# 20250814.net
KiCad netlist of a schematic drawn in EasyEDA Pro
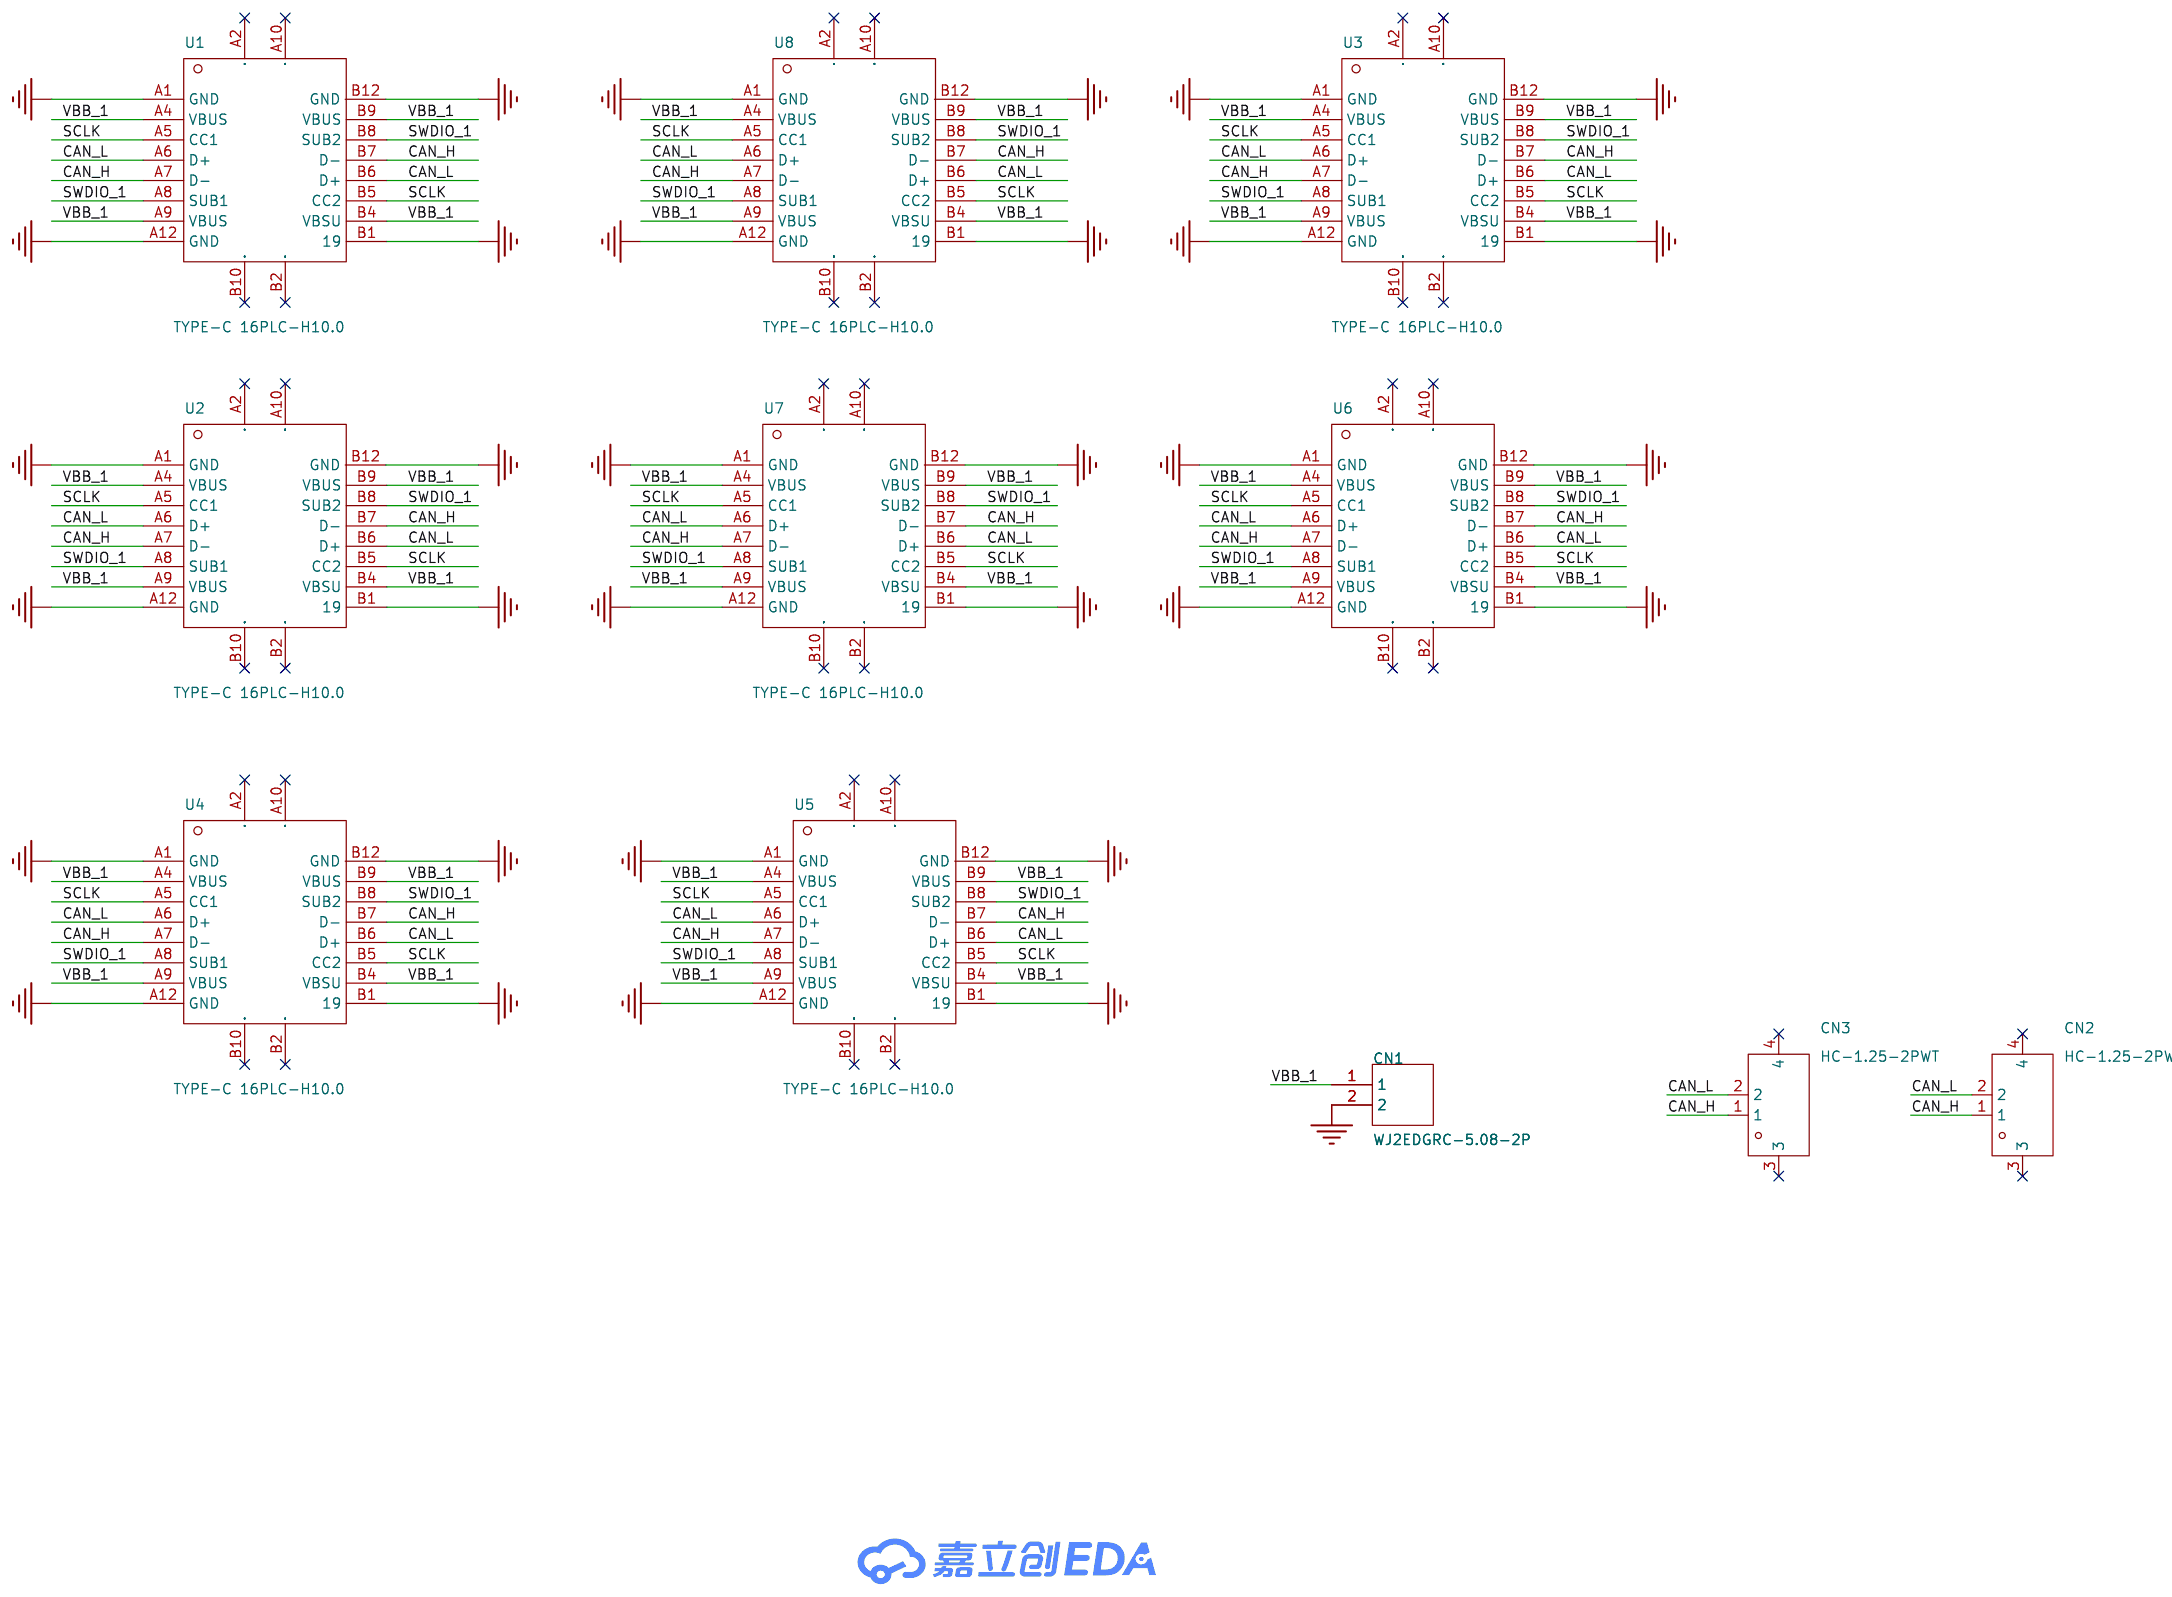
[diagram p0: schematic sheet]

(export (version "E")
  (design (tool "Eeschema 10.0.6"))
  (components
    (comp (ref "CN1")
      (value "WJ2EDGRC-5.08-2P")
      (footprint "easyedapro:CONN-TH_2P-P5.08_WJ2EDGRC-5.08-2P")
      (fields (field (name "Manufacturer") "KANGNEX(康奈克斯电气)"))
      (libsource (lib "easyedapro") (part "WJ2EDGRC-5.08-2P"))
    )
    (comp (ref "CN2")
      (value "HC-1.25-2PWT")
      (footprint "easyedapro:CONN-SMD_2P-P1.25-HC-1.25-2PWT")
      (fields (field (name "Manufacturer") "HCTL(华灿天禄)"))
      (libsource (lib "easyedapro") (part "HC-1.25-2PWT"))
    )
    (comp (ref "CN3")
      (value "HC-1.25-2PWT")
      (footprint "easyedapro:CONN-SMD_2P-P1.25-HC-1.25-2PWT")
      (fields (field (name "Manufacturer") "HCTL(华灿天禄)"))
      (libsource (lib "easyedapro") (part "HC-1.25-2PWT"))
    )
    (comp (ref "U1")
      (value "TYPE-C 16PLC-H10.0")
      (footprint "easyedapro:TYPE-C-TH_16PLC-H10.0")
      (fields (field (name "Manufacturer") "SHOU HAN(首韩)"))
      (libsource (lib "easyedapro") (part "TYPE-C 16PLC-H10.0"))
    )
    (comp (ref "U2")
      (value "TYPE-C 16PLC-H10.0")
      (footprint "easyedapro:TYPE-C-TH_16PLC-H10.0")
      (fields (field (name "Manufacturer") "SHOU HAN(首韩)"))
      (libsource (lib "easyedapro") (part "TYPE-C 16PLC-H10.0"))
    )
    (comp (ref "U3")
      (value "TYPE-C 16PLC-H10.0")
      (footprint "easyedapro:TYPE-C-TH_16PLC-H10.0")
      (fields (field (name "Manufacturer") "SHOU HAN(首韩)"))
      (libsource (lib "easyedapro") (part "TYPE-C 16PLC-H10.0"))
    )
    (comp (ref "U4")
      (value "TYPE-C 16PLC-H10.0")
      (footprint "easyedapro:TYPE-C-TH_16PLC-H10.0")
      (fields (field (name "Manufacturer") "SHOU HAN(首韩)"))
      (libsource (lib "easyedapro") (part "TYPE-C 16PLC-H10.0"))
    )
    (comp (ref "U5")
      (value "TYPE-C 16PLC-H10.0")
      (footprint "easyedapro:TYPE-C-TH_16PLC-H10.0")
      (fields (field (name "Manufacturer") "SHOU HAN(首韩)"))
      (libsource (lib "easyedapro") (part "TYPE-C 16PLC-H10.0"))
    )
    (comp (ref "U6")
      (value "TYPE-C 16PLC-H10.0")
      (footprint "easyedapro:TYPE-C-TH_16PLC-H10.0")
      (fields (field (name "Manufacturer") "SHOU HAN(首韩)"))
      (libsource (lib "easyedapro") (part "TYPE-C 16PLC-H10.0"))
    )
    (comp (ref "U7")
      (value "TYPE-C 16PLC-H10.0")
      (footprint "easyedapro:TYPE-C-TH_16PLC-H10.0")
      (fields (field (name "Manufacturer") "SHOU HAN(首韩)"))
      (libsource (lib "easyedapro") (part "TYPE-C 16PLC-H10.0"))
    )
    (comp (ref "U8")
      (value "TYPE-C 16PLC-H10.0")
      (footprint "easyedapro:TYPE-C-TH_16PLC-H10.0")
      (fields (field (name "Manufacturer") "SHOU HAN(首韩)"))
      (libsource (lib "easyedapro") (part "TYPE-C 16PLC-H10.0"))
    )
  )
  (nets
    (net (code "1") (name "/CAN_H") (class "Default")
      (node (ref "CN2") (pin "1") (pinfunction "1_1") (pintype "unspecified"))
      (node (ref "CN3") (pin "1") (pinfunction "1_1") (pintype "unspecified"))
      (node (ref "U1") (pin "A7") (pinfunction "D-_A7") (pintype "input"))
      (node (ref "U1") (pin "B7") (pinfunction "D-_B7") (pintype "input"))
      (node (ref "U2") (pin "A7") (pinfunction "D-_A7") (pintype "input"))
      (node (ref "U2") (pin "B7") (pinfunction "D-_B7") (pintype "input"))
      (node (ref "U3") (pin "A7") (pinfunction "D-_A7") (pintype "input"))
      (node (ref "U3") (pin "B7") (pinfunction "D-_B7") (pintype "input"))
      (node (ref "U4") (pin "A7") (pinfunction "D-_A7") (pintype "input"))
      (node (ref "U4") (pin "B7") (pinfunction "D-_B7") (pintype "input"))
      (node (ref "U5") (pin "A7") (pinfunction "D-_A7") (pintype "input"))
      (node (ref "U5") (pin "B7") (pinfunction "D-_B7") (pintype "input"))
      (node (ref "U6") (pin "A7") (pinfunction "D-_A7") (pintype "input"))
      (node (ref "U6") (pin "B7") (pinfunction "D-_B7") (pintype "input"))
      (node (ref "U7") (pin "A7") (pinfunction "D-_A7") (pintype "input"))
      (node (ref "U7") (pin "B7") (pinfunction "D-_B7") (pintype "input"))
      (node (ref "U8") (pin "A7") (pinfunction "D-_A7") (pintype "input"))
      (node (ref "U8") (pin "B7") (pinfunction "D-_B7") (pintype "input"))
    )
    (net (code "2") (name "/CAN_L") (class "Default")
      (node (ref "CN2") (pin "2") (pinfunction "2_2") (pintype "unspecified"))
      (node (ref "CN3") (pin "2") (pinfunction "2_2") (pintype "unspecified"))
      (node (ref "U1") (pin "A6") (pinfunction "D+_A6") (pintype "input"))
      (node (ref "U1") (pin "B6") (pinfunction "D+_B6") (pintype "input"))
      (node (ref "U2") (pin "A6") (pinfunction "D+_A6") (pintype "input"))
      (node (ref "U2") (pin "B6") (pinfunction "D+_B6") (pintype "input"))
      (node (ref "U3") (pin "A6") (pinfunction "D+_A6") (pintype "input"))
      (node (ref "U3") (pin "B6") (pinfunction "D+_B6") (pintype "input"))
      (node (ref "U4") (pin "A6") (pinfunction "D+_A6") (pintype "input"))
      (node (ref "U4") (pin "B6") (pinfunction "D+_B6") (pintype "input"))
      (node (ref "U5") (pin "A6") (pinfunction "D+_A6") (pintype "input"))
      (node (ref "U5") (pin "B6") (pinfunction "D+_B6") (pintype "input"))
      (node (ref "U6") (pin "A6") (pinfunction "D+_A6") (pintype "input"))
      (node (ref "U6") (pin "B6") (pinfunction "D+_B6") (pintype "input"))
      (node (ref "U7") (pin "A6") (pinfunction "D+_A6") (pintype "input"))
      (node (ref "U7") (pin "B6") (pinfunction "D+_B6") (pintype "input"))
      (node (ref "U8") (pin "A6") (pinfunction "D+_A6") (pintype "input"))
      (node (ref "U8") (pin "B6") (pinfunction "D+_B6") (pintype "input"))
    )
    (net (code "3") (name "/SCLK") (class "Default")
      (node (ref "U1") (pin "A5") (pinfunction "CC1_A5") (pintype "input"))
      (node (ref "U1") (pin "B5") (pinfunction "CC2_B5") (pintype "input"))
      (node (ref "U2") (pin "A5") (pinfunction "CC1_A5") (pintype "input"))
      (node (ref "U2") (pin "B5") (pinfunction "CC2_B5") (pintype "input"))
      (node (ref "U3") (pin "A5") (pinfunction "CC1_A5") (pintype "input"))
      (node (ref "U3") (pin "B5") (pinfunction "CC2_B5") (pintype "input"))
      (node (ref "U4") (pin "A5") (pinfunction "CC1_A5") (pintype "input"))
      (node (ref "U4") (pin "B5") (pinfunction "CC2_B5") (pintype "input"))
      (node (ref "U5") (pin "A5") (pinfunction "CC1_A5") (pintype "input"))
      (node (ref "U5") (pin "B5") (pinfunction "CC2_B5") (pintype "input"))
      (node (ref "U6") (pin "A5") (pinfunction "CC1_A5") (pintype "input"))
      (node (ref "U6") (pin "B5") (pinfunction "CC2_B5") (pintype "input"))
      (node (ref "U7") (pin "A5") (pinfunction "CC1_A5") (pintype "input"))
      (node (ref "U7") (pin "B5") (pinfunction "CC2_B5") (pintype "input"))
      (node (ref "U8") (pin "A5") (pinfunction "CC1_A5") (pintype "input"))
      (node (ref "U8") (pin "B5") (pinfunction "CC2_B5") (pintype "input"))
    )
    (net (code "4") (name "/SWDIO_1") (class "Default")
      (node (ref "U1") (pin "A8") (pinfunction "SUB1_A8") (pintype "input"))
      (node (ref "U1") (pin "B8") (pinfunction "SUB2_B8") (pintype "input"))
      (node (ref "U2") (pin "A8") (pinfunction "SUB1_A8") (pintype "input"))
      (node (ref "U2") (pin "B8") (pinfunction "SUB2_B8") (pintype "input"))
      (node (ref "U3") (pin "A8") (pinfunction "SUB1_A8") (pintype "input"))
      (node (ref "U3") (pin "B8") (pinfunction "SUB2_B8") (pintype "input"))
      (node (ref "U4") (pin "A8") (pinfunction "SUB1_A8") (pintype "input"))
      (node (ref "U4") (pin "B8") (pinfunction "SUB2_B8") (pintype "input"))
      (node (ref "U5") (pin "A8") (pinfunction "SUB1_A8") (pintype "input"))
      (node (ref "U5") (pin "B8") (pinfunction "SUB2_B8") (pintype "input"))
      (node (ref "U6") (pin "A8") (pinfunction "SUB1_A8") (pintype "input"))
      (node (ref "U6") (pin "B8") (pinfunction "SUB2_B8") (pintype "input"))
      (node (ref "U7") (pin "A8") (pinfunction "SUB1_A8") (pintype "input"))
      (node (ref "U7") (pin "B8") (pinfunction "SUB2_B8") (pintype "input"))
      (node (ref "U8") (pin "A8") (pinfunction "SUB1_A8") (pintype "input"))
      (node (ref "U8") (pin "B8") (pinfunction "SUB2_B8") (pintype "input"))
    )
    (net (code "5") (name "/VBB_1") (class "Default")
      (node (ref "CN1") (pin "1") (pinfunction "1_1") (pintype "unspecified"))
      (node (ref "U1") (pin "A4") (pinfunction "VBUS_A4") (pintype "input"))
      (node (ref "U1") (pin "A9") (pinfunction "VBUS_A9") (pintype "input"))
      (node (ref "U1") (pin "B4") (pinfunction "VBSU_B4") (pintype "input"))
      (node (ref "U1") (pin "B9") (pinfunction "VBUS_B9") (pintype "input"))
      (node (ref "U2") (pin "A4") (pinfunction "VBUS_A4") (pintype "input"))
      (node (ref "U2") (pin "A9") (pinfunction "VBUS_A9") (pintype "input"))
      (node (ref "U2") (pin "B4") (pinfunction "VBSU_B4") (pintype "input"))
      (node (ref "U2") (pin "B9") (pinfunction "VBUS_B9") (pintype "input"))
      (node (ref "U3") (pin "A4") (pinfunction "VBUS_A4") (pintype "input"))
      (node (ref "U3") (pin "A9") (pinfunction "VBUS_A9") (pintype "input"))
      (node (ref "U3") (pin "B4") (pinfunction "VBSU_B4") (pintype "input"))
      (node (ref "U3") (pin "B9") (pinfunction "VBUS_B9") (pintype "input"))
      (node (ref "U4") (pin "A4") (pinfunction "VBUS_A4") (pintype "input"))
      (node (ref "U4") (pin "A9") (pinfunction "VBUS_A9") (pintype "input"))
      (node (ref "U4") (pin "B4") (pinfunction "VBSU_B4") (pintype "input"))
      (node (ref "U4") (pin "B9") (pinfunction "VBUS_B9") (pintype "input"))
      (node (ref "U5") (pin "A4") (pinfunction "VBUS_A4") (pintype "input"))
      (node (ref "U5") (pin "A9") (pinfunction "VBUS_A9") (pintype "input"))
      (node (ref "U5") (pin "B4") (pinfunction "VBSU_B4") (pintype "input"))
      (node (ref "U5") (pin "B9") (pinfunction "VBUS_B9") (pintype "input"))
      (node (ref "U6") (pin "A4") (pinfunction "VBUS_A4") (pintype "input"))
      (node (ref "U6") (pin "A9") (pinfunction "VBUS_A9") (pintype "input"))
      (node (ref "U6") (pin "B4") (pinfunction "VBSU_B4") (pintype "input"))
      (node (ref "U6") (pin "B9") (pinfunction "VBUS_B9") (pintype "input"))
      (node (ref "U7") (pin "A4") (pinfunction "VBUS_A4") (pintype "input"))
      (node (ref "U7") (pin "A9") (pinfunction "VBUS_A9") (pintype "input"))
      (node (ref "U7") (pin "B4") (pinfunction "VBSU_B4") (pintype "input"))
      (node (ref "U7") (pin "B9") (pinfunction "VBUS_B9") (pintype "input"))
      (node (ref "U8") (pin "A4") (pinfunction "VBUS_A4") (pintype "input"))
      (node (ref "U8") (pin "A9") (pinfunction "VBUS_A9") (pintype "input"))
      (node (ref "U8") (pin "B4") (pinfunction "VBSU_B4") (pintype "input"))
      (node (ref "U8") (pin "B9") (pinfunction "VBUS_B9") (pintype "input"))
    )
    (net (code "6") (name "GND") (class "Default")
      (node (ref "CN1") (pin "2") (pinfunction "2_2") (pintype "unspecified"))
      (node (ref "U1") (pin "A1") (pinfunction "GND_A1") (pintype "input"))
      (node (ref "U1") (pin "A12") (pinfunction "GND_A12") (pintype "input"))
      (node (ref "U1") (pin "B1") (pinfunction "19_B1") (pintype "input"))
      (node (ref "U1") (pin "B12") (pinfunction "GND_B12") (pintype "input"))
      (node (ref "U2") (pin "A1") (pinfunction "GND_A1") (pintype "input"))
      (node (ref "U2") (pin "A12") (pinfunction "GND_A12") (pintype "input"))
      (node (ref "U2") (pin "B1") (pinfunction "19_B1") (pintype "input"))
      (node (ref "U2") (pin "B12") (pinfunction "GND_B12") (pintype "input"))
      (node (ref "U3") (pin "A1") (pinfunction "GND_A1") (pintype "input"))
      (node (ref "U3") (pin "A12") (pinfunction "GND_A12") (pintype "input"))
      (node (ref "U3") (pin "B1") (pinfunction "19_B1") (pintype "input"))
      (node (ref "U3") (pin "B12") (pinfunction "GND_B12") (pintype "input"))
      (node (ref "U4") (pin "A1") (pinfunction "GND_A1") (pintype "input"))
      (node (ref "U4") (pin "A12") (pinfunction "GND_A12") (pintype "input"))
      (node (ref "U4") (pin "B1") (pinfunction "19_B1") (pintype "input"))
      (node (ref "U4") (pin "B12") (pinfunction "GND_B12") (pintype "input"))
      (node (ref "U5") (pin "A1") (pinfunction "GND_A1") (pintype "input"))
      (node (ref "U5") (pin "A12") (pinfunction "GND_A12") (pintype "input"))
      (node (ref "U5") (pin "B1") (pinfunction "19_B1") (pintype "input"))
      (node (ref "U5") (pin "B12") (pinfunction "GND_B12") (pintype "input"))
      (node (ref "U6") (pin "A1") (pinfunction "GND_A1") (pintype "input"))
      (node (ref "U6") (pin "A12") (pinfunction "GND_A12") (pintype "input"))
      (node (ref "U6") (pin "B1") (pinfunction "19_B1") (pintype "input"))
      (node (ref "U6") (pin "B12") (pinfunction "GND_B12") (pintype "input"))
      (node (ref "U7") (pin "A1") (pinfunction "GND_A1") (pintype "input"))
      (node (ref "U7") (pin "A12") (pinfunction "GND_A12") (pintype "input"))
      (node (ref "U7") (pin "B1") (pinfunction "19_B1") (pintype "input"))
      (node (ref "U7") (pin "B12") (pinfunction "GND_B12") (pintype "input"))
      (node (ref "U8") (pin "A1") (pinfunction "GND_A1") (pintype "input"))
      (node (ref "U8") (pin "A12") (pinfunction "GND_A12") (pintype "input"))
      (node (ref "U8") (pin "B1") (pinfunction "19_B1") (pintype "input"))
      (node (ref "U8") (pin "B12") (pinfunction "GND_B12") (pintype "input"))
    )
    (net (code "7") (name "unconnected-(CN2-Pad3)") (class "Default")
      (node (ref "CN2") (pin "3") (pinfunction "3_3") (pintype "unspecified+no_connect"))
    )
    (net (code "8") (name "unconnected-(CN2-Pad4)") (class "Default")
      (node (ref "CN2") (pin "4") (pinfunction "4_4") (pintype "unspecified+no_connect"))
    )
    (net (code "9") (name "unconnected-(CN3-Pad3)") (class "Default")
      (node (ref "CN3") (pin "3") (pinfunction "3_3") (pintype "unspecified+no_connect"))
    )
    (net (code "10") (name "unconnected-(CN3-Pad4)") (class "Default")
      (node (ref "CN3") (pin "4") (pinfunction "4_4") (pintype "unspecified+no_connect"))
    )
    (net (code "11") (name "unconnected-(U1-GND1-PadA2)") (class "Default")
      (node (ref "U1") (pin "A2") (pinfunction "GND1_A2") (pintype "input+no_connect"))
    )
    (net (code "12") (name "unconnected-(U1-GND2-PadA10)") (class "Default")
      (node (ref "U1") (pin "A10") (pinfunction "GND2_A10") (pintype "input+no_connect"))
    )
    (net (code "13") (name "unconnected-(U1-GND3-PadB10)") (class "Default")
      (node (ref "U1") (pin "B10") (pinfunction "GND3_B10") (pintype "input+no_connect"))
    )
    (net (code "14") (name "unconnected-(U1-GND4-PadB2)") (class "Default")
      (node (ref "U1") (pin "B2") (pinfunction "GND4_B2") (pintype "input+no_connect"))
    )
    (net (code "15") (name "unconnected-(U2-GND1-PadA2)") (class "Default")
      (node (ref "U2") (pin "A2") (pinfunction "GND1_A2") (pintype "input+no_connect"))
    )
    (net (code "16") (name "unconnected-(U2-GND2-PadA10)") (class "Default")
      (node (ref "U2") (pin "A10") (pinfunction "GND2_A10") (pintype "input+no_connect"))
    )
    (net (code "17") (name "unconnected-(U2-GND3-PadB10)") (class "Default")
      (node (ref "U2") (pin "B10") (pinfunction "GND3_B10") (pintype "input+no_connect"))
    )
    (net (code "18") (name "unconnected-(U2-GND4-PadB2)") (class "Default")
      (node (ref "U2") (pin "B2") (pinfunction "GND4_B2") (pintype "input+no_connect"))
    )
    (net (code "19") (name "unconnected-(U3-GND1-PadA2)") (class "Default")
      (node (ref "U3") (pin "A2") (pinfunction "GND1_A2") (pintype "input+no_connect"))
    )
    (net (code "20") (name "unconnected-(U3-GND2-PadA10)") (class "Default")
      (node (ref "U3") (pin "A10") (pinfunction "GND2_A10") (pintype "input+no_connect"))
    )
    (net (code "21") (name "unconnected-(U3-GND3-PadB10)") (class "Default")
      (node (ref "U3") (pin "B10") (pinfunction "GND3_B10") (pintype "input+no_connect"))
    )
    (net (code "22") (name "unconnected-(U3-GND4-PadB2)") (class "Default")
      (node (ref "U3") (pin "B2") (pinfunction "GND4_B2") (pintype "input+no_connect"))
    )
    (net (code "23") (name "unconnected-(U4-GND1-PadA2)") (class "Default")
      (node (ref "U4") (pin "A2") (pinfunction "GND1_A2") (pintype "input+no_connect"))
    )
    (net (code "24") (name "unconnected-(U4-GND2-PadA10)") (class "Default")
      (node (ref "U4") (pin "A10") (pinfunction "GND2_A10") (pintype "input+no_connect"))
    )
    (net (code "25") (name "unconnected-(U4-GND3-PadB10)") (class "Default")
      (node (ref "U4") (pin "B10") (pinfunction "GND3_B10") (pintype "input+no_connect"))
    )
    (net (code "26") (name "unconnected-(U4-GND4-PadB2)") (class "Default")
      (node (ref "U4") (pin "B2") (pinfunction "GND4_B2") (pintype "input+no_connect"))
    )
    (net (code "27") (name "unconnected-(U5-GND1-PadA2)") (class "Default")
      (node (ref "U5") (pin "A2") (pinfunction "GND1_A2") (pintype "input+no_connect"))
    )
    (net (code "28") (name "unconnected-(U5-GND2-PadA10)") (class "Default")
      (node (ref "U5") (pin "A10") (pinfunction "GND2_A10") (pintype "input+no_connect"))
    )
    (net (code "29") (name "unconnected-(U5-GND3-PadB10)") (class "Default")
      (node (ref "U5") (pin "B10") (pinfunction "GND3_B10") (pintype "input+no_connect"))
    )
    (net (code "30") (name "unconnected-(U5-GND4-PadB2)") (class "Default")
      (node (ref "U5") (pin "B2") (pinfunction "GND4_B2") (pintype "input+no_connect"))
    )
    (net (code "31") (name "unconnected-(U6-GND1-PadA2)") (class "Default")
      (node (ref "U6") (pin "A2") (pinfunction "GND1_A2") (pintype "input+no_connect"))
    )
    (net (code "32") (name "unconnected-(U6-GND2-PadA10)") (class "Default")
      (node (ref "U6") (pin "A10") (pinfunction "GND2_A10") (pintype "input+no_connect"))
    )
    (net (code "33") (name "unconnected-(U6-GND3-PadB10)") (class "Default")
      (node (ref "U6") (pin "B10") (pinfunction "GND3_B10") (pintype "input+no_connect"))
    )
    (net (code "34") (name "unconnected-(U6-GND4-PadB2)") (class "Default")
      (node (ref "U6") (pin "B2") (pinfunction "GND4_B2") (pintype "input+no_connect"))
    )
    (net (code "35") (name "unconnected-(U7-GND1-PadA2)") (class "Default")
      (node (ref "U7") (pin "A2") (pinfunction "GND1_A2") (pintype "input+no_connect"))
    )
    (net (code "36") (name "unconnected-(U7-GND2-PadA10)") (class "Default")
      (node (ref "U7") (pin "A10") (pinfunction "GND2_A10") (pintype "input+no_connect"))
    )
    (net (code "37") (name "unconnected-(U7-GND3-PadB10)") (class "Default")
      (node (ref "U7") (pin "B10") (pinfunction "GND3_B10") (pintype "input+no_connect"))
    )
    (net (code "38") (name "unconnected-(U7-GND4-PadB2)") (class "Default")
      (node (ref "U7") (pin "B2") (pinfunction "GND4_B2") (pintype "input+no_connect"))
    )
    (net (code "39") (name "unconnected-(U8-GND1-PadA2)") (class "Default")
      (node (ref "U8") (pin "A2") (pinfunction "GND1_A2") (pintype "input+no_connect"))
    )
    (net (code "40") (name "unconnected-(U8-GND2-PadA10)") (class "Default")
      (node (ref "U8") (pin "A10") (pinfunction "GND2_A10") (pintype "input+no_connect"))
    )
    (net (code "41") (name "unconnected-(U8-GND3-PadB10)") (class "Default")
      (node (ref "U8") (pin "B10") (pinfunction "GND3_B10") (pintype "input+no_connect"))
    )
    (net (code "42") (name "unconnected-(U8-GND4-PadB2)") (class "Default")
      (node (ref "U8") (pin "B2") (pinfunction "GND4_B2") (pintype "input+no_connect"))
    )
  )
)
